# Filter-14.net
KiCad netlist of a schematic drawn in Altium Designer
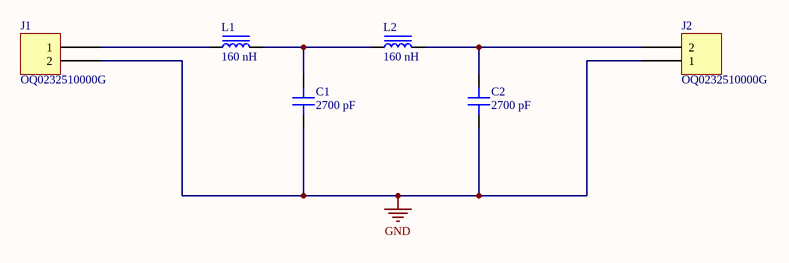
[diagram p0: Filter-14.SchDoc]

(export (version "E")
  (design (tool "Eeschema 10.0.6"))
  (components
    (comp (ref "C1")
      (value "2700 pF")
      (footprint "CAP 0603_1608")
      (description "CAP CER 2700PF 25V NP0 0603")
      (fields (field (name "PART NUMBER") "C0603C272F3GAC7867") (field (name "MANUFACTURER") "KEMET"))
      (libsource (lib "Celestial Altium Library - altium_library") (part "Capacitor"))
    )
    (comp (ref "C2")
      (value "2700 pF")
      (footprint "CAP 0603_1608")
      (description "CAP CER 2700PF 25V NP0 0603")
      (fields (field (name "PART NUMBER") "C0603C272F3GAC7867") (field (name "MANUFACTURER") "KEMET"))
      (libsource (lib "Celestial Altium Library - altium_library") (part "Capacitor"))
    )
    (comp (ref "J1")
      (value "OQ0232510000G")
      (footprint "FCI 06-381-2PIN")
      (description "TERM BLOCK HDR 2POS 90DEG 3.81MM")
      (fields (field (name "MANUFACTURER") "Amphenol Anytek"))
      (libsource (lib "") (part "2 Pin_1"))
    )
    (comp (ref "J2")
      (value "OQ0232510000G")
      (footprint "FCI 06-381-2PIN")
      (description "TERM BLOCK HDR 2POS 90DEG 3.81MM")
      (fields (field (name "MANUFACTURER") "Amphenol Anytek"))
      (libsource (lib "Celestial Altium Library - altium_library") (part "2 Pin"))
    )
    (comp (ref "L1")
      (value "160 nH")
      (footprint "IND 0402_1005 RF WW")
      (description "FIXED IND 160NH 480MA 330MOHM SM")
      (fields
        (field (name "PART NUMBER") "LQW15CNR16J00D")
        (field (name "MANUFACTURER") "Murata Electronics")
      )
      (libsource (lib "Celestial Altium Library - altium_library") (part "Inductor"))
    )
    (comp (ref "L2")
      (value "160 nH")
      (footprint "IND 0402_1005 RF WW")
      (description "FIXED IND 160NH 480MA 330MOHM SM")
      (fields
        (field (name "PART NUMBER") "LQW15CNR16J00D")
        (field (name "MANUFACTURER") "Murata Electronics")
      )
      (libsource (lib "Celestial Altium Library - altium_library") (part "Inductor"))
    )
  )
  (nets
    (net (code "1") (name "GND") (class "Default")
      (node (ref "C1") (pin "1") (pinfunction "1_1") (pintype "passive"))
      (node (ref "C2") (pin "1") (pinfunction "1_1") (pintype "passive"))
      (node (ref "J1") (pin "2") (pinfunction "2_2") (pintype "passive"))
      (node (ref "J2") (pin "1") (pinfunction "1_1") (pintype "passive"))
    )
    (net (code "2") (name "Net-(C1-Pad2)") (class "Default")
      (node (ref "C1") (pin "2") (pinfunction "2_2") (pintype "passive"))
      (node (ref "L1") (pin "2") (pinfunction "2_2") (pintype "passive"))
      (node (ref "L2") (pin "1") (pinfunction "1_1") (pintype "passive"))
    )
    (net (code "3") (name "Net-(C2-Pad2)") (class "Default")
      (node (ref "C2") (pin "2") (pinfunction "2_2") (pintype "passive"))
      (node (ref "J2") (pin "2") (pinfunction "2_2") (pintype "passive"))
      (node (ref "L2") (pin "2") (pinfunction "2_2") (pintype "passive"))
    )
    (net (code "4") (name "Net-(J1-Pad1)") (class "Default")
      (node (ref "J1") (pin "1") (pinfunction "1_1") (pintype "passive"))
      (node (ref "L1") (pin "1") (pinfunction "1_1") (pintype "passive"))
    )
  )
)
